# External.net
KiCad netlist of a schematic drawn in Altium Designer
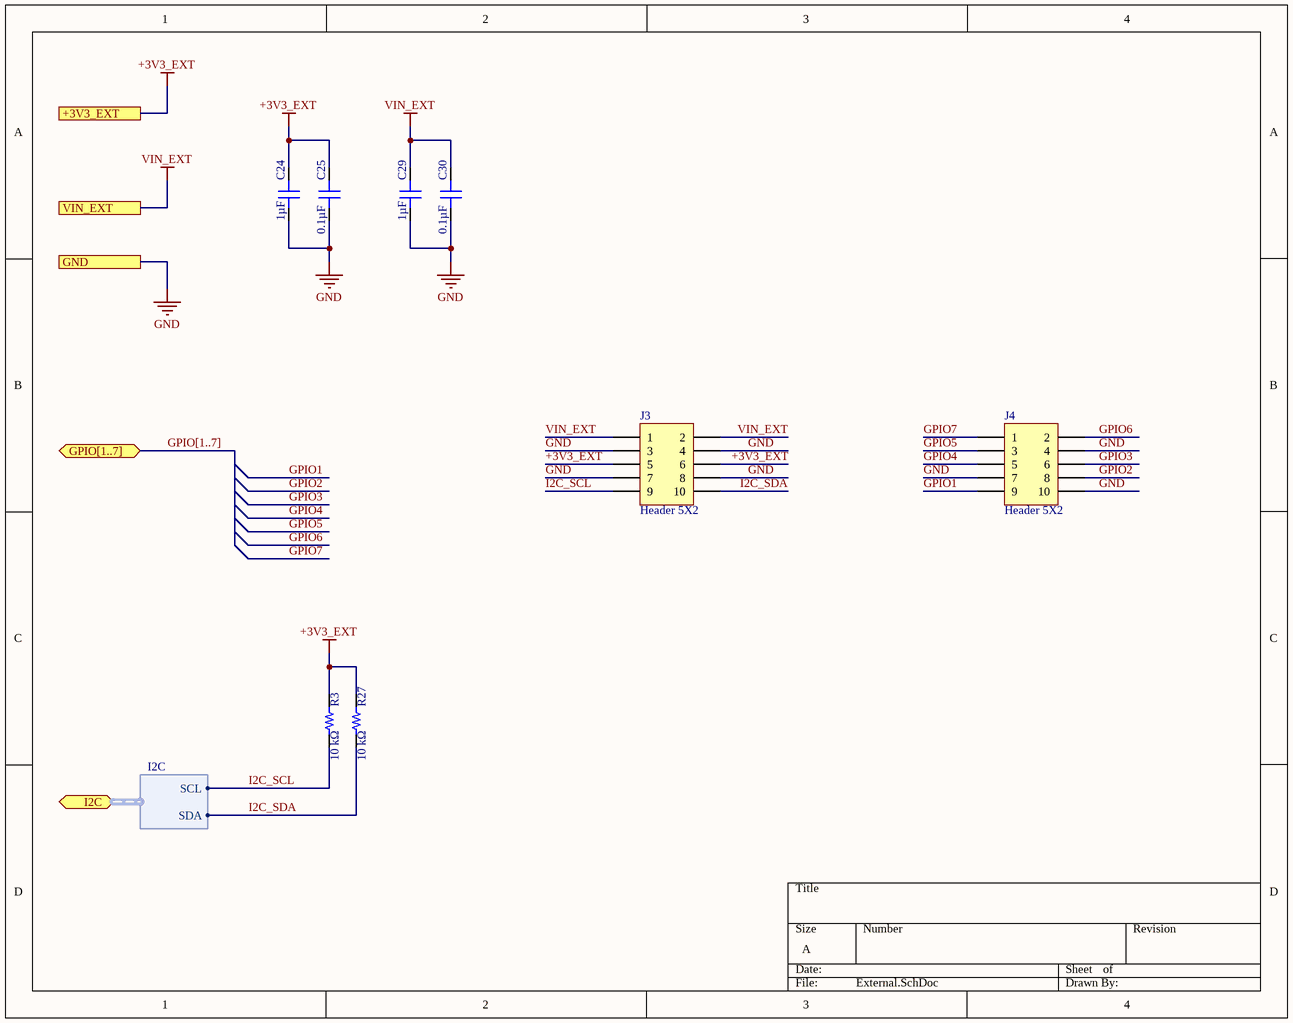
[diagram p0: External.SchDoc]

(export (version "E")
  (design (tool "Eeschema 10.0.6"))
  (components
    (comp (ref "C24")
      (value "1µF")
      (footprint "CAP 0402_1005")
      (description "CAP CER 1UF 10V X5R 0402")
      (fields (field (name "PART NUMBER") "0402ZD105KAT2A") (field (name "MANUFACTURER") "AVX Corporation"))
      (libsource (lib "Generic Altium Database") (part "Capacitor"))
    )
    (comp (ref "C25")
      (value "0.1µF")
      (footprint "CAP 0402_1005")
      (description "CAP CER 0.1UF 25V X7R 0402")
      (fields (field (name "PART NUMBER") "04023C104JAT2A") (field (name "MANUFACTURER") "AVX Corporation"))
      (libsource (lib "Generic Altium Database") (part "Capacitor"))
    )
    (comp (ref "C29")
      (value "1µF")
      (footprint "CAP 0402_1005")
      (description "CAP CER 1UF 10V X5R 0402")
      (fields (field (name "PART NUMBER") "0402ZD105KAT2A") (field (name "MANUFACTURER") "AVX Corporation"))
      (libsource (lib "Generic Altium Database") (part "Capacitor"))
    )
    (comp (ref "C30")
      (value "0.1µF")
      (footprint "CAP 0402_1005")
      (description "CAP CER 0.1UF 25V X7R 0402")
      (fields (field (name "PART NUMBER") "04023C104JAT2A") (field (name "MANUFACTURER") "AVX Corporation"))
      (libsource (lib "Generic Altium Database") (part "Capacitor"))
    )
    (comp (ref "J3")
      (value "Header 5X2")
      (footprint "HDR2X5")
      (description "Header, 5-Pin, Dual row")
      (fields (field (name "PUBLISHER") "Altium Limited"))
      (libsource (lib "Miscellaneous Connectors") (part "Header 5X2"))
    )
    (comp (ref "J4")
      (value "Header 5X2")
      (footprint "HDR2X5")
      (description "Header, 5-Pin, Dual row")
      (fields (field (name "PUBLISHER") "Altium Limited"))
      (libsource (lib "Miscellaneous Connectors") (part "Header 5X2"))
    )
    (comp (ref "R3")
      (value "10 kΩ")
      (footprint "RES 0402_1005")
      (description "RES SMD 10K OHM 1% 1/16W 0402")
      (fields (field (name "PART NUMBER") "AC0402FR-0710KL") (field (name "MANUFACTURER") "Yageo"))
      (libsource (lib "Generic Altium Database") (part "Resistor"))
    )
    (comp (ref "R27")
      (value "10 kΩ")
      (footprint "RES 0402_1005")
      (description "RES SMD 10K OHM 1% 1/16W 0402")
      (fields (field (name "PART NUMBER") "AC0402FR-0710KL") (field (name "MANUFACTURER") "Yageo"))
      (libsource (lib "Generic Altium Database") (part "Resistor"))
    )
  )
  (nets
    (net (code "2") (name "+3V3_EXT") (class "Default")
      (node (ref "C24") (pin "1") (pinfunction "1_1") (pintype "passive"))
      (node (ref "C25") (pin "1") (pinfunction "1_1") (pintype "passive"))
      (node (ref "J3") (pin "5") (pinfunction "5_5") (pintype "passive"))
      (node (ref "J3") (pin "6") (pinfunction "6_6") (pintype "passive"))
      (node (ref "R27") (pin "1") (pinfunction "1_1") (pintype "passive"))
      (node (ref "R3") (pin "1") (pinfunction "1_1") (pintype "passive"))
    )
    (net (code "3") (name "/GPIO1") (class "Default")
      (node (ref "J4") (pin "9") (pinfunction "9_9") (pintype "passive"))
    )
    (net (code "4") (name "/GPIO2") (class "Default")
      (node (ref "J4") (pin "8") (pinfunction "8_8") (pintype "passive"))
    )
    (net (code "5") (name "/GPIO3") (class "Default")
      (node (ref "J4") (pin "6") (pinfunction "6_6") (pintype "passive"))
    )
    (net (code "6") (name "/GPIO4") (class "Default")
      (node (ref "J4") (pin "5") (pinfunction "5_5") (pintype "passive"))
    )
    (net (code "7") (name "/GPIO5") (class "Default")
      (node (ref "J4") (pin "3") (pinfunction "3_3") (pintype "passive"))
    )
    (net (code "8") (name "/GPIO6") (class "Default")
      (node (ref "J4") (pin "2") (pinfunction "2_2") (pintype "passive"))
    )
    (net (code "9") (name "/GPIO7") (class "Default")
      (node (ref "J4") (pin "1") (pinfunction "1_1") (pintype "passive"))
    )
    (net (code "11") (name "/I2C_SCL") (class "Default")
      (node (ref "J3") (pin "9") (pinfunction "9_9") (pintype "passive"))
      (node (ref "R3") (pin "2") (pinfunction "2_2") (pintype "passive"))
    )
    (net (code "12") (name "/I2C_SDA") (class "Default")
      (node (ref "J3") (pin "10") (pinfunction "10_10") (pintype "passive"))
      (node (ref "R27") (pin "2") (pinfunction "2_2") (pintype "passive"))
    )
    (net (code "14") (name "GND") (class "Default")
      (node (ref "C24") (pin "2") (pinfunction "2_2") (pintype "passive"))
      (node (ref "C25") (pin "2") (pinfunction "2_2") (pintype "passive"))
      (node (ref "C29") (pin "2") (pinfunction "2_2") (pintype "passive"))
      (node (ref "C30") (pin "2") (pinfunction "2_2") (pintype "passive"))
      (node (ref "J3") (pin "3") (pinfunction "3_3") (pintype "passive"))
      (node (ref "J3") (pin "4") (pinfunction "4_4") (pintype "passive"))
      (node (ref "J3") (pin "7") (pinfunction "7_7") (pintype "passive"))
      (node (ref "J3") (pin "8") (pinfunction "8_8") (pintype "passive"))
      (node (ref "J4") (pin "10") (pinfunction "10_10") (pintype "passive"))
      (node (ref "J4") (pin "4") (pinfunction "4_4") (pintype "passive"))
      (node (ref "J4") (pin "7") (pinfunction "7_7") (pintype "passive"))
    )
    (net (code "15") (name "VIN_EXT") (class "Default")
      (node (ref "C29") (pin "1") (pinfunction "1_1") (pintype "passive"))
      (node (ref "C30") (pin "1") (pinfunction "1_1") (pintype "passive"))
      (node (ref "J3") (pin "1") (pinfunction "1_1") (pintype "passive"))
      (node (ref "J3") (pin "2") (pinfunction "2_2") (pintype "passive"))
    )
  )
)
